# Teensylu-1_3.net
KiCad netlist of a schematic drawn in EAGLE
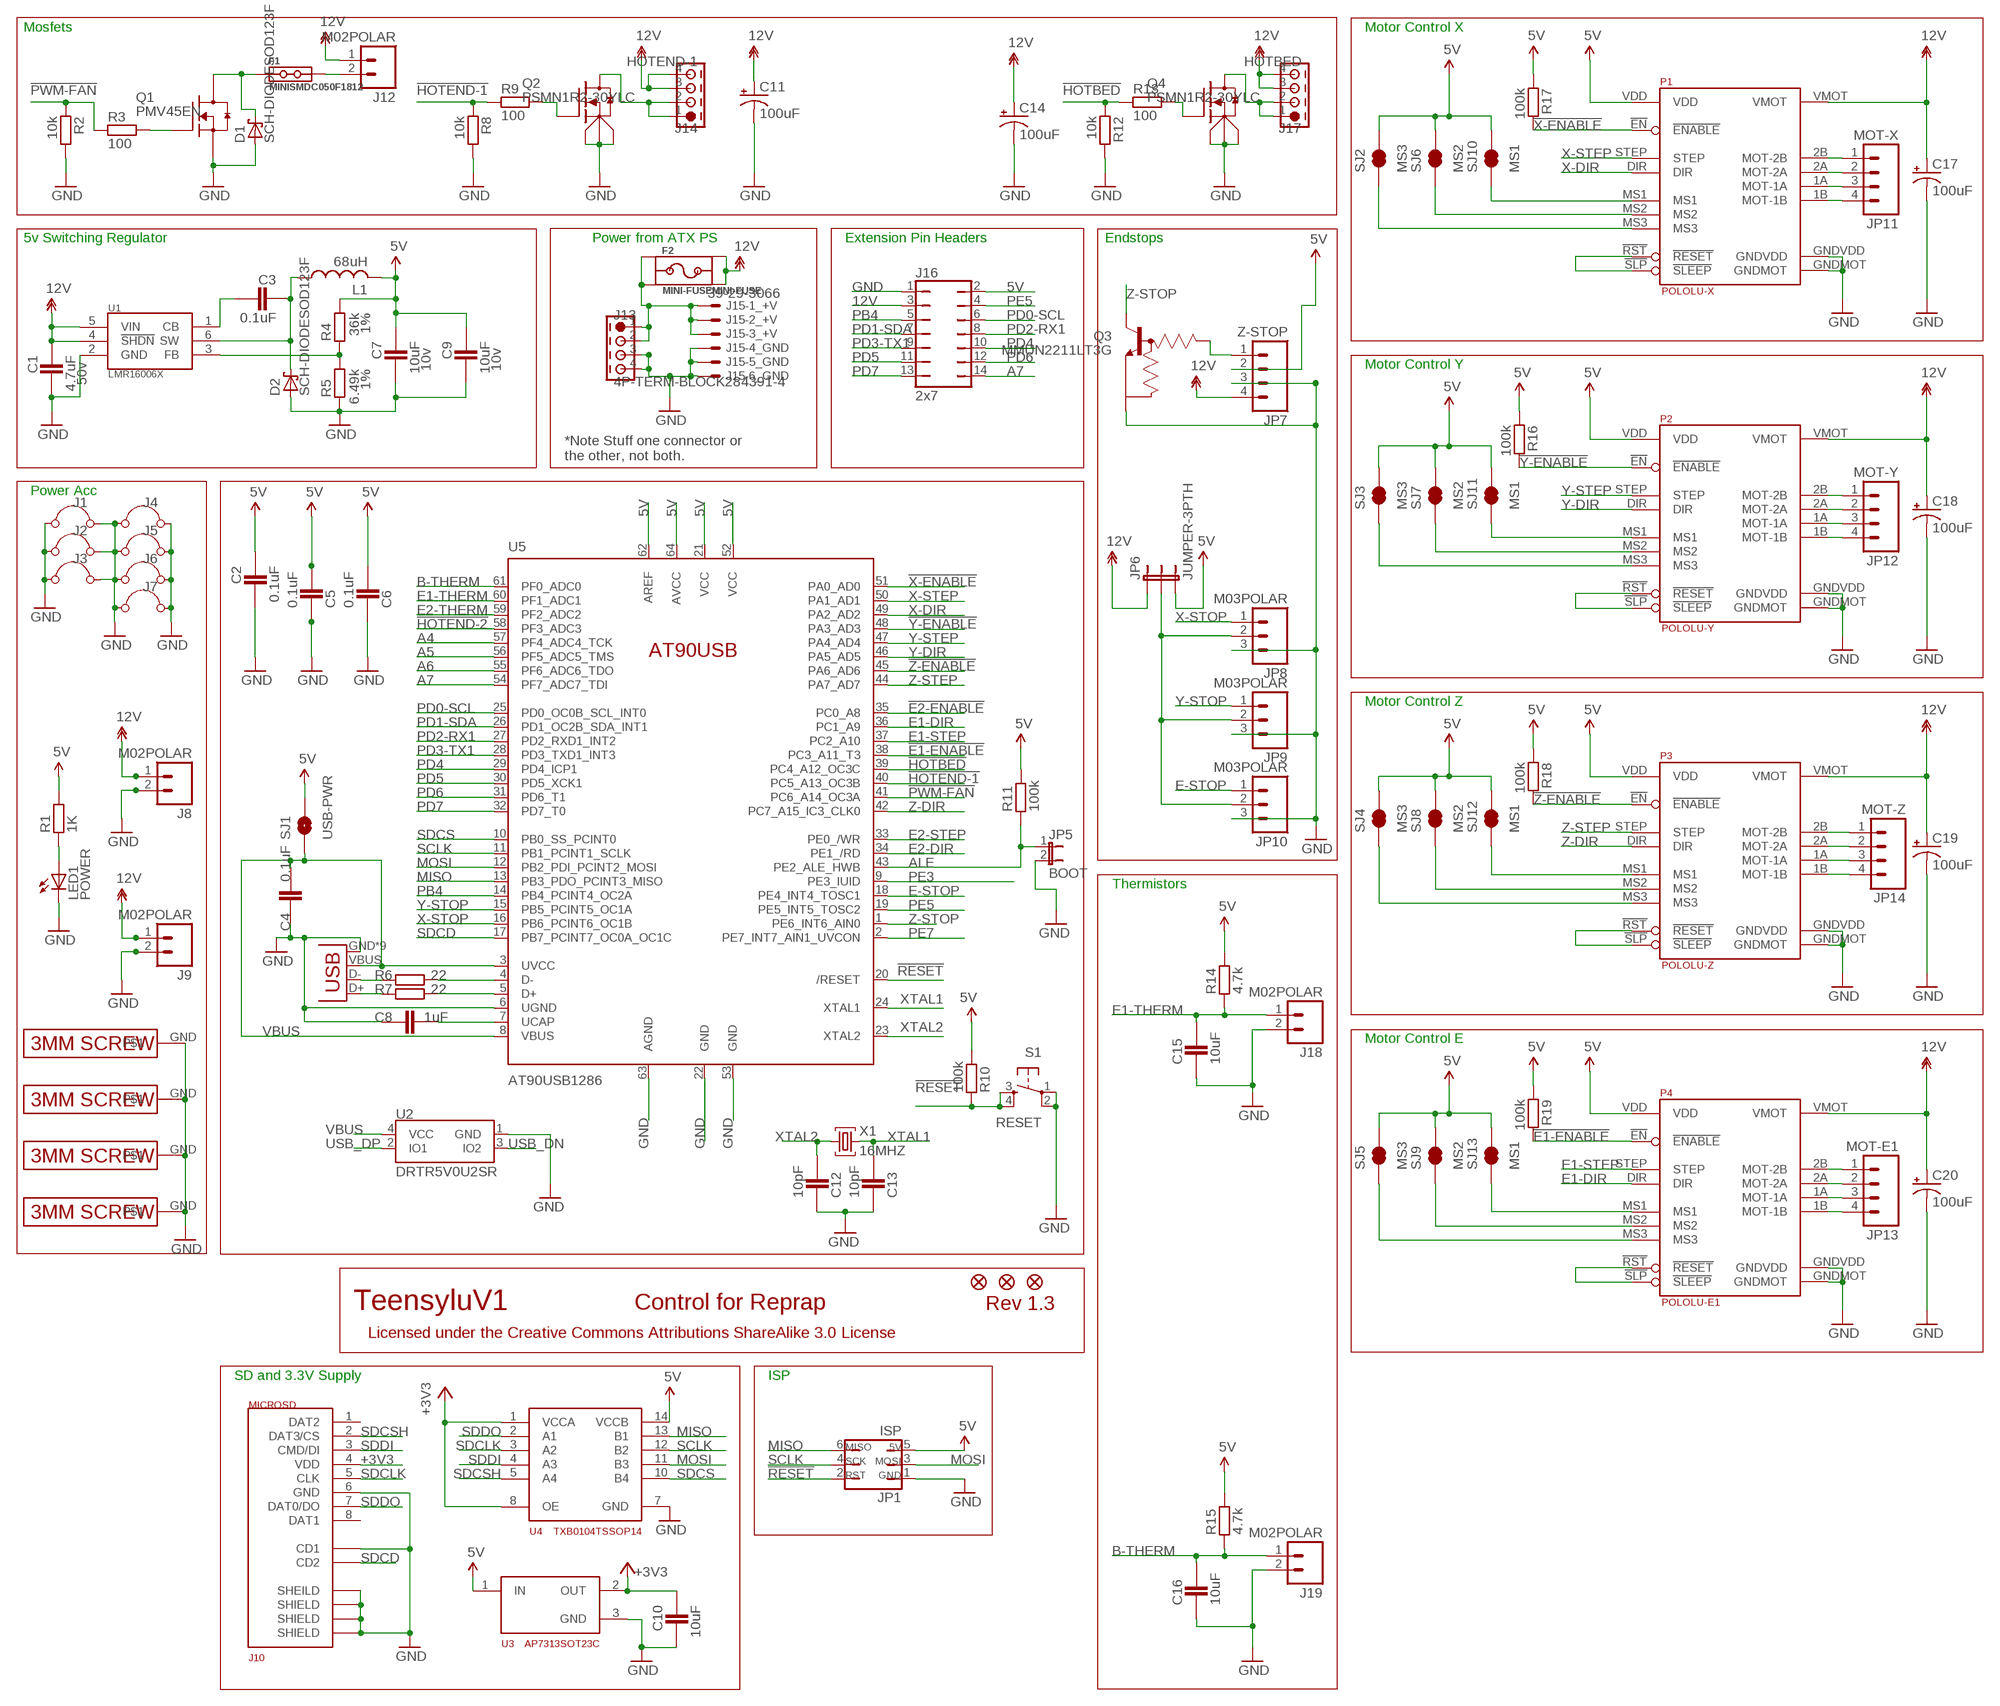
[diagram p0: schematic, sheet 1]

(export (version "E")
  (design (tool "Eeschema 10.0.6"))
  (components
    (comp (ref "C1")
      (value "4.7uF")
      (footprint "eagle-import:CAPC3215X168N")
      (fields
        (field (name "MANUFACTURER") "Yaiyo Yuden")
        (field (name "MANUFACTURER_PART_NUMBER") "UMK316AB7475KL-T")
        (field (name "TOLERANCE") "10%")
        (field (name "VDC") "50v")
      )
      (libsource (lib "eagle-import") (part "CAPACITOR_1206"))
    )
    (comp (ref "C2")
      (value "0.1uF")
      (footprint "eagle-import:CAPC1608X92N")
      (fields
        (field (name "MANUFACTURER") "Murata")
        (field (name "MANUFACTURER_PART_NUMBER") "GRM188R71C104KA01D")
        (field (name "TOLERANCE") "10%")
      )
      (libsource (lib "eagle-import") (part "CAPACITOR_0603"))
    )
    (comp (ref "C3")
      (value "0.1uF")
      (footprint "eagle-import:CAPC1608X92N")
      (fields
        (field (name "MANUFACTURER") "Samsung")
        (field (name "MANUFACTURER_PART_NUMBER") "CL10B104KB8NNNC")
        (field (name "TOLERANCE") "10%")
      )
      (libsource (lib "eagle-import") (part "CAPACITOR_0603"))
    )
    (comp (ref "C4")
      (value "0.1uF")
      (footprint "eagle-import:CAPC1608X92N")
      (fields
        (field (name "MANUFACTURER") "Murata")
        (field (name "MANUFACTURER_PART_NUMBER") "GRM188R71C104KA01D")
        (field (name "TOLERANCE") "10%")
      )
      (libsource (lib "eagle-import") (part "CAPACITOR_0603"))
    )
    (comp (ref "C5")
      (value "0.1uF")
      (footprint "eagle-import:CAPC1608X92N")
      (fields
        (field (name "MANUFACTURER") "Murata")
        (field (name "MANUFACTURER_PART_NUMBER") "GRM188R71C104KA01D")
        (field (name "TOLERANCE") "10%")
      )
      (libsource (lib "eagle-import") (part "CAPACITOR_0603"))
    )
    (comp (ref "C6")
      (value "0.1uF")
      (footprint "eagle-import:CAPC1608X92N")
      (fields
        (field (name "MANUFACTURER") "Murata")
        (field (name "MANUFACTURER_PART_NUMBER") "GRM188R71C104KA01D")
        (field (name "TOLERANCE") "10%")
      )
      (libsource (lib "eagle-import") (part "CAPACITOR_0603"))
    )
    (comp (ref "C7")
      (value "10uF")
      (footprint "eagle-import:CAPC2012X145AN")
      (fields
        (field (name "MANUFACTURER") "Murata")
        (field (name "MANUFACTURER_PART_NUMBER") "GRM21BR71A106KE51L")
        (field (name "TOLERANCE") "10%")
        (field (name "VDC") "10v")
      )
      (libsource (lib "eagle-import") (part "CAPACITOR_0805"))
    )
    (comp (ref "C8")
      (value "1uF")
      (footprint "eagle-import:CAPC1608X92N")
      (fields
        (field (name "MANUFACTURER") "Samsung")
        (field (name "MANUFACTURER_PART_NUMBER") "CL10A105MO8NNNC")
        (field (name "TOLERANCE") "20%")
      )
      (libsource (lib "eagle-import") (part "CAPACITOR_0603"))
    )
    (comp (ref "C9")
      (value "10uF")
      (footprint "eagle-import:CAPC2012X145AN")
      (fields
        (field (name "MANUFACTURER") "Murata")
        (field (name "MANUFACTURER_PART_NUMBER") "GRM21BR71A106KE51L")
        (field (name "TOLERANCE") "10%")
        (field (name "VDC") "10v")
      )
      (libsource (lib "eagle-import") (part "CAPACITOR_0805"))
    )
    (comp (ref "C10")
      (value "10uF")
      (footprint "eagle-import:CAPC1608X92N")
      (fields
        (field (name "MANUFACTURER") "Murata")
        (field (name "MANUFACTURER_PART_NUMBER") "GRM188R61C106MA73D")
        (field (name "TOLERANCE") "20%")
      )
      (libsource (lib "eagle-import") (part "CAPACITOR_0603"))
    )
    (comp (ref "C11")
      (value "100uF")
      (footprint "eagle-import:PANASONIC_D")
      (fields
        (field (name "MANUFACTURER") "Panasonic")
        (field (name "MANUFACTURER_PART_NUMBER") "EEE-FTH101XAP")
        (field (name "TOLERANCE") "20%")
      )
      (libsource (lib "eagle-import") (part "CPOL-USD"))
    )
    (comp (ref "C12")
      (value "10pF")
      (footprint "eagle-import:CAPC1608X92N")
      (fields
        (field (name "MANUFACTURER") "Samsung")
        (field (name "MANUFACTURER_PART_NUMBER") "CL10C100JB8NCNC")
        (field (name "TOLERANCE") "5%")
      )
      (libsource (lib "eagle-import") (part "CAPACITOR_0603"))
    )
    (comp (ref "C13")
      (value "10pF")
      (footprint "eagle-import:CAPC1608X92N")
      (fields
        (field (name "MANUFACTURER") "Samsung")
        (field (name "MANUFACTURER_PART_NUMBER") "CL10C100JB8NCNC")
        (field (name "TOLERANCE") "5%")
      )
      (libsource (lib "eagle-import") (part "CAPACITOR_0603"))
    )
    (comp (ref "C14")
      (value "100uF")
      (footprint "eagle-import:PANASONIC_D")
      (fields
        (field (name "MANUFACTURER") "Panasonic")
        (field (name "MANUFACTURER_PART_NUMBER") "EEE-FTH101XAP")
        (field (name "TOLERANCE") "20%")
      )
      (libsource (lib "eagle-import") (part "CPOL-USD"))
    )
    (comp (ref "C15")
      (value "10uF")
      (footprint "eagle-import:CAPC1608X92N")
      (fields
        (field (name "MANUFACTURER") "Murata")
        (field (name "MANUFACTURER_PART_NUMBER") "GRM188R61C106MA73D")
        (field (name "TOLERANCE") "20%")
      )
      (libsource (lib "eagle-import") (part "CAPACITOR_0603"))
    )
    (comp (ref "C16")
      (value "10uF")
      (footprint "eagle-import:CAPC1608X92N")
      (fields
        (field (name "MANUFACTURER") "Murata")
        (field (name "MANUFACTURER_PART_NUMBER") "GRM188R61C106MA73D")
        (field (name "TOLERANCE") "20%")
      )
      (libsource (lib "eagle-import") (part "CAPACITOR_0603"))
    )
    (comp (ref "C17")
      (value "100uF")
      (footprint "eagle-import:PANASONIC_D")
      (fields
        (field (name "MANUFACTURER") "Panasonic")
        (field (name "MANUFACTURER_PART_NUMBER") "EEE-FTH101XAP")
        (field (name "TOLERANCE") "20%")
      )
      (libsource (lib "eagle-import") (part "CPOL-USD"))
    )
    (comp (ref "C18")
      (value "100uF")
      (footprint "eagle-import:PANASONIC_D")
      (fields
        (field (name "MANUFACTURER") "Panasonic")
        (field (name "MANUFACTURER_PART_NUMBER") "EEE-FTH101XAP")
        (field (name "TOLERANCE") "20%")
      )
      (libsource (lib "eagle-import") (part "CPOL-USD"))
    )
    (comp (ref "C19")
      (value "100uF")
      (footprint "eagle-import:PANASONIC_D")
      (fields
        (field (name "MANUFACTURER") "Panasonic")
        (field (name "MANUFACTURER_PART_NUMBER") "EEE-FTH101XAP")
        (field (name "TOLERANCE") "20%")
      )
      (libsource (lib "eagle-import") (part "CPOL-USD"))
    )
    (comp (ref "C20")
      (value "100uF")
      (footprint "eagle-import:PANASONIC_D")
      (fields
        (field (name "MANUFACTURER") "Panasonic")
        (field (name "MANUFACTURER_PART_NUMBER") "EEE-FTH101XAP")
        (field (name "TOLERANCE") "20%")
      )
      (libsource (lib "eagle-import") (part "CPOL-USD"))
    )
    (comp (ref "D1")
      (value "SCH-DIODESOD123F")
      (footprint "eagle-import:SOD123F")
      (fields
        (field (name "MANUFACTURER") "NXP Semiconductors")
        (field (name "MANUFACTURER_PART_NUMBER") "PMEG4010CEH,115")
        (field (name "CURRENT") "1A")
        (field (name "MANUFACTURER_1") "NXP Semiconductors")
      )
      (libsource (lib "eagle-import") (part "SCH-DIODESOD123F"))
    )
    (comp (ref "D2")
      (value "SCH-DIODESOD123F")
      (footprint "eagle-import:SOD123F")
      (fields
        (field (name "MANUFACTURER") "NXP Semiconductors")
        (field (name "MANUFACTURER_PART_NUMBER") "PMEG4010CEH,115")
        (field (name "CURRENT") "1A")
        (field (name "MANUFACTURER_1") "NXP Semiconductors")
        (field (name "MANUFACTURER_PART_NUMBER_1") "PMEG4010CEH,115")
        (field (name "REVERSE_VOLTAGE") "40V")
      )
      (libsource (lib "eagle-import") (part "SCH-DIODESOD123F"))
    )
    (comp (ref "F1")
      (value "MINISMDC050F1812")
      (footprint "eagle-import:MINISMDC")
      (fields
        (field (name "MANUFACTURER") "TE Connectivity")
        (field (name "MANUFACTURER_PART_NUMBER") "MINISMDC050F-2")
      )
      (libsource (lib "eagle-import") (part "MINISMDC050F1812"))
    )
    (comp (ref "F2")
      (value "MINI-FUSEMINI-FUSE")
      (footprint "eagle-import:MINI_FUSE")
      (fields (field (name "MANUFACTURER") "Keystone") (field (name "MANUFACTURER_PART_NUMBER") "3568"))
      (libsource (lib "eagle-import") (part "MINI-FUSEMINI-FUSE"))
    )
    (comp (ref "J1")
      (value "22ga")
      (footprint "eagle-import:WJ_01_08")
      (description "22ga jumper wire")
      (libsource (lib "eagle-import") (part "WIRE_JUMPER-0.1"))
    )
    (comp (ref "J2")
      (value "22ga")
      (footprint "eagle-import:WJ_01_08")
      (description "22ga jumper wire")
      (libsource (lib "eagle-import") (part "WIRE_JUMPER-0.1"))
    )
    (comp (ref "J3")
      (value "22ga")
      (footprint "eagle-import:WJ_01_08")
      (description "22ga jumper wire")
      (libsource (lib "eagle-import") (part "WIRE_JUMPER-0.1"))
    )
    (comp (ref "J4")
      (value "22ga")
      (footprint "eagle-import:WJ_01_08")
      (description "22ga jumper wire")
      (libsource (lib "eagle-import") (part "WIRE_JUMPER-0.1"))
    )
    (comp (ref "J5")
      (value "22ga")
      (footprint "eagle-import:WJ_01_08")
      (description "22ga jumper wire")
      (libsource (lib "eagle-import") (part "WIRE_JUMPER-0.1"))
    )
    (comp (ref "J6")
      (value "22ga")
      (footprint "eagle-import:WJ_01_08")
      (description "22ga jumper wire")
      (libsource (lib "eagle-import") (part "WIRE_JUMPER-0.1"))
    )
    (comp (ref "J7")
      (value "22ga")
      (footprint "eagle-import:WJ_01_08")
      (description "22ga jumper wire")
      (libsource (lib "eagle-import") (part "WIRE_JUMPER-0.1"))
    )
    (comp (ref "J8")
      (value "M02POLAR")
      (footprint "eagle-import:MOLEX-1X2")
      (description "CONN HEADER 2POS .100 VERT TIN")
      (fields (field (name "MANUFACTURER") "Molex") (field (name "MANUFACTURER_PART_NUMBER") "0022272021"))
      (libsource (lib "eagle-import") (part "M02POLAR"))
    )
    (comp (ref "J9")
      (value "M02POLAR")
      (footprint "eagle-import:MOLEX-1X2")
      (description "CONN HEADER 2POS .100 VERT TIN")
      (fields (field (name "MANUFACTURER") "Molex") (field (name "MANUFACTURER_PART_NUMBER") "0022272021"))
      (libsource (lib "eagle-import") (part "M02POLAR"))
    )
    (comp (ref "J10")
      (value "MICROSD")
      (footprint "eagle-import:AMPHENOL-MICROSD")
      (description "CONN MICRO SD CARD PUSH-PULL R/A")
      (fields
        (field (name "MANUFACTURER") "Amphenol")
        (field (name "MANUFACTURER_PART_NUMBER") "114-00841-68")
      )
      (libsource (lib "eagle-import") (part "MICROSD"))
    )
    (comp (ref "J11")
      (value "USB-MICRO-PTH")
      (footprint "eagle-import:USB-MICROB-PTH")
      (fields (field (name "MANUFACTURER") "FCI") (field (name "MANUFACTURER_PART_NUMBER") "10118194-0001LF"))
      (libsource (lib "eagle-import") (part "USB-MICRO-PTH"))
    )
    (comp (ref "J12")
      (value "M02POLAR")
      (footprint "eagle-import:MOLEX-1X2")
      (description "CONN HEADER 2POS .100 VERT TIN")
      (fields (field (name "MANUFACTURER") "Molex") (field (name "MANUFACTURER_PART_NUMBER") "0022272021"))
      (libsource (lib "eagle-import") (part "M02POLAR"))
    )
    (comp (ref "J13")
      (value "4P-TERM-BLOCK284391-4")
      (footprint "eagle-import:284391-4")
      (fields
        (field (name "MANUFACTURER") "TE Connectivity")
        (field (name "MANUFACTURER_PART_NUMBER") "284391-4")
      )
      (libsource (lib "eagle-import") (part "4P-TERM-BLOCK284391-4"))
    )
    (comp (ref "J14")
      (value "HOTEND-1")
      (footprint "eagle-import:284391-4")
      (fields
        (field (name "MANUFACTURER") "TE Connectivity")
        (field (name "MANUFACTURER_PART_NUMBER") "284391-4")
      )
      (libsource (lib "eagle-import") (part "4P-TERM-BLOCK284391-4"))
    )
    (comp (ref "J15")
      (value "39-29-3066")
      (footprint "eagle-import:39-29-3066")
      (fields (field (name "MANUFACTURER") "Molex") (field (name "MANUFACTURER_PART_NUMBER") "0039293066"))
      (libsource (lib "eagle-import") (part "39-29-3066"))
    )
    (comp (ref "J16")
      (value "2x7")
      (footprint "eagle-import:JP7Q")
      (description "DIL VERTICAL PC TAIL PIN HEADER")
      (fields (field (name "MANUFACTURER") "Harwin") (field (name "MANUFACTURER_PART_NUMBER") "M20-9980746"))
      (libsource (lib "eagle-import") (part "JP7Q"))
    )
    (comp (ref "J17")
      (value "HOTBED")
      (footprint "eagle-import:284391-4")
      (fields
        (field (name "MANUFACTURER") "TE Connectivity")
        (field (name "MANUFACTURER_PART_NUMBER") "284391-4")
      )
      (libsource (lib "eagle-import") (part "4P-TERM-BLOCK284391-4"))
    )
    (comp (ref "J18")
      (value "M02POLAR")
      (footprint "eagle-import:MOLEX-1X2")
      (description "CONN HEADER 2POS .100 VERT TIN")
      (fields (field (name "MANUFACTURER") "Molex") (field (name "MANUFACTURER_PART_NUMBER") "0022272021"))
      (libsource (lib "eagle-import") (part "M02POLAR"))
    )
    (comp (ref "J19")
      (value "M02POLAR")
      (footprint "eagle-import:MOLEX-1X2")
      (description "CONN HEADER 2POS .100 VERT TIN")
      (fields (field (name "MANUFACTURER") "Molex") (field (name "MANUFACTURER_PART_NUMBER") "0022272021"))
      (libsource (lib "eagle-import") (part "M02POLAR"))
    )
    (comp (ref "JP1")
      (value "ISP")
      (footprint "eagle-import:ISP")
      (libsource (lib "eagle-import") (part "PROGHEADER"))
    )
    (comp (ref "JP2")
      (value "FIDUCIAL1X2.5")
      (footprint "eagle-import:FIDUCIAL-1X2.5")
      (libsource (lib "eagle-import") (part "FIDUCIAL1X2.5"))
    )
    (comp (ref "JP3")
      (value "FIDUCIAL1X2.5")
      (footprint "eagle-import:FIDUCIAL-1X2.5")
      (libsource (lib "eagle-import") (part "FIDUCIAL1X2.5"))
    )
    (comp (ref "JP4")
      (value "FIDUCIAL1X2.5")
      (footprint "eagle-import:FIDUCIAL-1X2.5")
      (libsource (lib "eagle-import") (part "FIDUCIAL1X2.5"))
    )
    (comp (ref "JP5")
      (value "BOOT")
      (footprint "eagle-import:1X02")
      (description "SIL VERTICAL PC TAIL PIN HEADER")
      (fields (field (name "MANUFACTURER") "Harwin") (field (name "MANUFACTURER_PART_NUMBER") "M20-9990246"))
      (libsource (lib "eagle-import") (part "JUMPER-2PTH"))
    )
    (comp (ref "JP6")
      (value "JUMPER-3PTH")
      (footprint "eagle-import:1X03")
      (libsource (lib "eagle-import") (part "JUMPER-3PTH"))
    )
    (comp (ref "JP7")
      (value "Z-STOP")
      (footprint "eagle-import:MOLEX-1X4")
      (fields (field (name "MANUFACTURER") "Molex") (field (name "MANUFACTURER_PART_NUMBER") "0022272041"))
      (libsource (lib "eagle-import") (part "M04POLAR"))
    )
    (comp (ref "JP8")
      (value "M03POLAR")
      (footprint "eagle-import:MOLEX-1X3")
      (description "CONN HEADER 3POS .100 VERT TIN")
      (fields (field (name "MANUFACTURER") "Molex") (field (name "MANUFACTURER_PART_NUMBER") "0022272031"))
      (libsource (lib "eagle-import") (part "M03POLAR"))
    )
    (comp (ref "JP9")
      (value "M03POLAR")
      (footprint "eagle-import:MOLEX-1X3")
      (description "CONN HEADER 3POS .100 VERT TIN")
      (fields (field (name "MANUFACTURER") "Molex") (field (name "MANUFACTURER_PART_NUMBER") "0022272031"))
      (libsource (lib "eagle-import") (part "M03POLAR"))
    )
    (comp (ref "JP10")
      (value "M03POLAR")
      (footprint "eagle-import:MOLEX-1X3")
      (description "CONN HEADER 3POS .100 VERT TIN")
      (fields (field (name "MANUFACTURER") "Molex") (field (name "MANUFACTURER_PART_NUMBER") "0022272031"))
      (libsource (lib "eagle-import") (part "M03POLAR"))
    )
    (comp (ref "JP11")
      (value "MOT-X")
      (footprint "eagle-import:MOLEX-1X4")
      (fields (field (name "MANUFACTURER") "Molex") (field (name "MANUFACTURER_PART_NUMBER") "0022272041"))
      (libsource (lib "eagle-import") (part "M04POLAR"))
    )
    (comp (ref "JP12")
      (value "MOT-Y")
      (footprint "eagle-import:MOLEX-1X4")
      (fields (field (name "MANUFACTURER") "Molex") (field (name "MANUFACTURER_PART_NUMBER") "0022272041"))
      (libsource (lib "eagle-import") (part "M04POLAR"))
    )
    (comp (ref "JP13")
      (value "MOT-E1")
      (footprint "eagle-import:MOLEX-1X4")
      (fields (field (name "MANUFACTURER") "Molex") (field (name "MANUFACTURER_PART_NUMBER") "0022272041"))
      (libsource (lib "eagle-import") (part "M04POLAR"))
    )
    (comp (ref "JP14")
      (value "MOT-Z")
      (footprint "eagle-import:MOLEX-1X4")
      (fields (field (name "MANUFACTURER") "Molex") (field (name "MANUFACTURER_PART_NUMBER") "0022272041"))
      (libsource (lib "eagle-import") (part "M04POLAR"))
    )
    (comp (ref "L1")
      (value "68uH")
      (footprint "eagle-import:SRN6045")
      (fields
        (field (name "MANUFACTURER") "Bourns")
        (field (name "MANUFACTURER_PART_NUMBER") "SRN6045-680M")
        (field (name "MANUFACTURER_1") "Bourns")
        (field (name "MANUFACTURER_PART_NUMBER_1") "SRN6045-680M")
      )
      (libsource (lib "eagle-import") (part "INDUCTORSRN6045"))
    )
    (comp (ref "LED1")
      (value "POWER")
      (footprint "eagle-import:CHIPLED_0805")
      (fields
        (field (name "MANUFACTURER") "Kingbright")
        (field (name "MANUFACTURER_PART_NUMBER") "APT2012SGC")
      )
      (libsource (lib "eagle-import") (part "LEDCHIPLED_0805"))
    )
    (comp (ref "P1")
      (value "POLOLU-X")
      (footprint "eagle-import:POLOLU-STEPPER-PTH")
      (libsource (lib "eagle-import") (part "POLOLU-ALLEGRO"))
    )
    (comp (ref "P2")
      (value "POLOLU-Y")
      (footprint "eagle-import:POLOLU-STEPPER-PTH")
      (libsource (lib "eagle-import") (part "POLOLU-ALLEGRO"))
    )
    (comp (ref "P3")
      (value "POLOLU-Z")
      (footprint "eagle-import:POLOLU-STEPPER-PTH")
      (libsource (lib "eagle-import") (part "POLOLU-ALLEGRO"))
    )
    (comp (ref "P4")
      (value "POLOLU-E1")
      (footprint "eagle-import:POLOLU-STEPPER-PTH")
      (libsource (lib "eagle-import") (part "POLOLU-ALLEGRO"))
    )
    (comp (ref "Q1")
      (value "PMV45EN")
      (footprint "eagle-import:SOT23C")
      (fields
        (field (name "MANUFACTURER") "International Rectifier")
        (field (name "MANUFACTURER_PART_NUMBER") "IRLML2060TRPBF")
        (field (name "VOLTAGE") "60V")
      )
      (libsource (lib "eagle-import") (part "MOSFET-NCH_SOT-23"))
    )
    (comp (ref "Q2")
      (value "PSMN1R2-30YLC")
      (footprint "eagle-import:LFPACK-POWERPAK-SO8")
      (fields
        (field (name "MANUFACTURER") "NXP Semiconductors")
        (field (name "MANUFACTURER_PART_NUMBER") "PSMN1R2-30YLC,115")
        (field (name "VOLTAGE") "30V")
      )
      (libsource (lib "eagle-import") (part "PSMN1R2-30YLCPOWERPACK-S08"))
    )
    (comp (ref "Q3")
      (value "MMUN2211LT3G")
      (footprint "eagle-import:SOT23C")
      (description "TRANS PREBIAS NPN 246MW SOT23-3")
      (fields (field (name "MANUFACTURER") "ON Semiconductor"))
      (libsource (lib "eagle-import") (part "TRANSISTOR_NPN_BIASSOT23C"))
    )
    (comp (ref "Q4")
      (value "PSMN1R2-30YLC")
      (footprint "eagle-import:LFPACK-POWERPAK-SO8")
      (fields
        (field (name "MANUFACTURER") "NXP Semiconductors")
        (field (name "MANUFACTURER_PART_NUMBER") "PSMN1R2-30YLC,115")
        (field (name "VOLTAGE") "30V")
      )
      (libsource (lib "eagle-import") (part "PSMN1R2-30YLCPOWERPACK-S08"))
    )
    (comp (ref "R1")
      (value "1K")
      (footprint "eagle-import:RESC1608X55N")
      (libsource (lib "eagle-import") (part "RESISTOR_0603"))
    )
    (comp (ref "R2")
      (value "10k")
      (footprint "eagle-import:RESC1608X55N")
      (libsource (lib "eagle-import") (part "RESISTOR_0603"))
    )
    (comp (ref "R3")
      (value "100")
      (footprint "eagle-import:RESC1608X55N")
      (libsource (lib "eagle-import") (part "RESISTOR_0603"))
    )
    (comp (ref "R4")
      (value "36k")
      (footprint "eagle-import:RESC1608X55N")
      (fields (field (name "TOLERANCE") "1%"))
      (libsource (lib "eagle-import") (part "RESISTOR_0603"))
    )
    (comp (ref "R5")
      (value "6.49k")
      (footprint "eagle-import:RESC1608X55N")
      (fields (field (name "TOLERANCE") "1%"))
      (libsource (lib "eagle-import") (part "RESISTOR_0603"))
    )
    (comp (ref "R6")
      (value "22")
      (footprint "eagle-import:RESC1608X55N")
      (libsource (lib "eagle-import") (part "RESISTOR_0603"))
    )
    (comp (ref "R7")
      (value "22")
      (footprint "eagle-import:RESC1608X55N")
      (libsource (lib "eagle-import") (part "RESISTOR_0603"))
    )
    (comp (ref "R8")
      (value "10k")
      (footprint "eagle-import:RESC1608X55N")
      (libsource (lib "eagle-import") (part "RESISTOR_0603"))
    )
    (comp (ref "R9")
      (value "100")
      (footprint "eagle-import:RESC1608X55N")
      (libsource (lib "eagle-import") (part "RESISTOR_0603"))
    )
    (comp (ref "R10")
      (value "100k")
      (footprint "eagle-import:RESC1608X55N")
      (libsource (lib "eagle-import") (part "RESISTOR_0603"))
    )
    (comp (ref "R11")
      (value "100k")
      (footprint "eagle-import:RESC1608X55N")
      (libsource (lib "eagle-import") (part "RESISTOR_0603"))
    )
    (comp (ref "R12")
      (value "10k")
      (footprint "eagle-import:RESC1608X55N")
      (libsource (lib "eagle-import") (part "RESISTOR_0603"))
    )
    (comp (ref "R13")
      (value "100")
      (footprint "eagle-import:RESC1608X55N")
      (libsource (lib "eagle-import") (part "RESISTOR_0603"))
    )
    (comp (ref "R14")
      (value "4.7k")
      (footprint "eagle-import:RESC1608X55N")
      (libsource (lib "eagle-import") (part "RESISTOR_0603"))
    )
    (comp (ref "R15")
      (value "4.7k")
      (footprint "eagle-import:RESC1608X55N")
      (libsource (lib "eagle-import") (part "RESISTOR_0603"))
    )
    (comp (ref "R16")
      (value "100k")
      (footprint "eagle-import:RESC1608X55N")
      (libsource (lib "eagle-import") (part "RESISTOR_0603"))
    )
    (comp (ref "R17")
      (value "100k")
      (footprint "eagle-import:RESC1608X55N")
      (libsource (lib "eagle-import") (part "RESISTOR_0603"))
    )
    (comp (ref "R18")
      (value "100k")
      (footprint "eagle-import:RESC1608X55N")
      (libsource (lib "eagle-import") (part "RESISTOR_0603"))
    )
    (comp (ref "R19")
      (value "100k")
      (footprint "eagle-import:RESC1608X55N")
      (libsource (lib "eagle-import") (part "RESISTOR_0603"))
    )
    (comp (ref "S1")
      (value "RESET")
      (footprint "eagle-import:TACTILE_SWITCH_SMD")
      (fields (field (name "MANUFACTURER") "Bourns") (field (name "MANUFACTURER_PART_NUMBER") "7914J-1-000E"))
      (libsource (lib "eagle-import") (part "TAC_SWITCHSMD"))
    )
    (comp (ref "SCREW1")
      (value "3MM-SCREW")
      (footprint "eagle-import:PLATEDSCREW")
      (libsource (lib "eagle-import") (part "3MM-SCREW"))
    )
    (comp (ref "SCREW2")
      (value "3MM-SCREW")
      (footprint "eagle-import:PLATEDSCREW")
      (libsource (lib "eagle-import") (part "3MM-SCREW"))
    )
    (comp (ref "SCREW3")
      (value "3MM-SCREW")
      (footprint "eagle-import:PLATEDSCREW")
      (libsource (lib "eagle-import") (part "3MM-SCREW"))
    )
    (comp (ref "SCREW4")
      (value "3MM-SCREW")
      (footprint "eagle-import:PLATEDSCREW")
      (libsource (lib "eagle-import") (part "3MM-SCREW"))
    )
    (comp (ref "SJ1")
      (value "USB-PWR")
      (footprint "eagle-import:SJ_2S-NO")
      (libsource (lib "eagle-import") (part "SOLDERJUMPERNO"))
    )
    (comp (ref "SJ2")
      (value "MS3")
      (footprint "eagle-import:SJ_2S-TRACE")
      (libsource (lib "eagle-import") (part "SOLDERJUMPER-NCSJ-TRACE"))
    )
    (comp (ref "SJ3")
      (value "MS3")
      (footprint "eagle-import:SJ_2S-TRACE")
      (libsource (lib "eagle-import") (part "SOLDERJUMPER-NCSJ-TRACE"))
    )
    (comp (ref "SJ4")
      (value "MS3")
      (footprint "eagle-import:SJ_2S-TRACE")
      (libsource (lib "eagle-import") (part "SOLDERJUMPER-NCSJ-TRACE"))
    )
    (comp (ref "SJ5")
      (value "MS3")
      (footprint "eagle-import:SJ_2S-TRACE")
      (libsource (lib "eagle-import") (part "SOLDERJUMPER-NCSJ-TRACE"))
    )
    (comp (ref "SJ6")
      (value "MS2")
      (footprint "eagle-import:SJ_2S-TRACE")
      (libsource (lib "eagle-import") (part "SOLDERJUMPER-NCSJ-TRACE"))
    )
    (comp (ref "SJ7")
      (value "MS2")
      (footprint "eagle-import:SJ_2S-TRACE")
      (libsource (lib "eagle-import") (part "SOLDERJUMPER-NCSJ-TRACE"))
    )
    (comp (ref "SJ8")
      (value "MS2")
      (footprint "eagle-import:SJ_2S-TRACE")
      (libsource (lib "eagle-import") (part "SOLDERJUMPER-NCSJ-TRACE"))
    )
    (comp (ref "SJ9")
      (value "MS2")
      (footprint "eagle-import:SJ_2S-TRACE")
      (libsource (lib "eagle-import") (part "SOLDERJUMPER-NCSJ-TRACE"))
    )
    (comp (ref "SJ10")
      (value "MS1")
      (footprint "eagle-import:SJ_2S-TRACE")
      (libsource (lib "eagle-import") (part "SOLDERJUMPER-NCSJ-TRACE"))
    )
    (comp (ref "SJ11")
      (value "MS1")
      (footprint "eagle-import:SJ_2S-TRACE")
      (libsource (lib "eagle-import") (part "SOLDERJUMPER-NCSJ-TRACE"))
    )
    (comp (ref "SJ12")
      (value "MS1")
      (footprint "eagle-import:SJ_2S-TRACE")
      (libsource (lib "eagle-import") (part "SOLDERJUMPER-NCSJ-TRACE"))
    )
    (comp (ref "SJ13")
      (value "MS1")
      (footprint "eagle-import:SJ_2S-TRACE")
      (libsource (lib "eagle-import") (part "SOLDERJUMPER-NCSJ-TRACE"))
    )
    (comp (ref "U1")
      (value "LMR16006X")
      (footprint "eagle-import:TSOT6")
      (fields
        (field (name "MANUFACTURER") "Texas Instruments")
        (field (name "MANUFACTURER_PART_NUMBER") "LMR16006XDDCT")
      )
      (libsource (lib "eagle-import") (part "LMR16006X"))
    )
    (comp (ref "U2")
      (value "DRTR5V0U2SR")
      (footprint "eagle-import:SOT143-R")
      (fields
        (field (name "MANUFACTURER") "Diodes Incorporated")
        (field (name "MANUFACTURER_PART_NUMBER") "DTR5V0U2SR")
      )
      (libsource (lib "eagle-import") (part "DRTR5V0U2SR"))
    )
    (comp (ref "U3")
      (value "AP7313SOT23C")
      (footprint "eagle-import:SOT23C")
      (description "IC REG LDO 3.3V 0.15A SOT23-3")
      (fields
        (field (name "MANUFACTURER") "Diodes Incorporated")
        (field (name "MANUFACTURER_PART_NUMBER") "AP7313-33SAG-7")
      )
      (libsource (lib "eagle-import") (part "AP7313SOT23C"))
    )
    (comp (ref "U4")
      (value "TXB0104TSSOP14")
      (footprint "eagle-import:TSSOP14")
      (description "IC VOLT-LEVEL TRANSLATOR 14TSSOP")
      (fields
        (field (name "MANUFACTURER") "Texas Instruments")
        (field (name "MANUFACTURER_PART_NUMBER") "TXB0104PWR")
      )
      (libsource (lib "eagle-import") (part "TXB0104TSSOP14"))
    )
    (comp (ref "U5")
      (value "AT90USB1286")
      (footprint "eagle-import:TQFP64-2")
      (fields (field (name "MANUFACTURER") "Atmel"))
      (libsource (lib "eagle-import") (part "AT90USB"))
    )
    (comp (ref "X1")
      (value "16MHZ")
      (footprint "eagle-import:NDK-XTAL")
      (fields
        (field (name "MANUFACTURER") "NDK")
        (field (name "MANUFACTURER_PART_NUMBER") "NX5032GA-16.000000MHZ-LN-CD-1")
      )
      (libsource (lib "eagle-import") (part "XTAL"))
    )
  )
  (nets
    (net (code "1") (name "+3V3") (class "Default")
      (node (ref "C10") (pin "1") (pinfunction "1_1") (pintype "passive"))
      (node (ref "J10") (pin "4") (pinfunction "VDD_4") (pintype "power_in"))
      (node (ref "U3") (pin "2") (pinfunction "OUT_2") (pintype "power_in"))
      (node (ref "U4") (pin "1") (pinfunction "VCCA_1") (pintype "power_in"))
      (node (ref "U4") (pin "8") (pinfunction "OE_8") (pintype "input"))
    )
    (net (code "2") (name "/A4") (class "Default")
      (node (ref "U5") (pin "57") (pinfunction "PF4_ADC4_TCK_57") (pintype "bidirectional"))
    )
    (net (code "3") (name "/A5") (class "Default")
      (node (ref "U5") (pin "56") (pinfunction "PF5_ADC5_TMS_56") (pintype "bidirectional"))
    )
    (net (code "4") (name "/A6") (class "Default")
      (node (ref "U5") (pin "55") (pinfunction "PF6_ADC6_TDO_55") (pintype "bidirectional"))
    )
    (net (code "5") (name "/A7") (class "Default")
      (node (ref "J16") (pin "14") (pinfunction "14_14") (pintype "passive"))
      (node (ref "U5") (pin "54") (pinfunction "PF7_ADC7_TDI_54") (pintype "bidirectional"))
    )
    (net (code "6") (name "/ALE") (class "Default")
      (node (ref "JP5") (pin "1") (pinfunction "1_1") (pintype "passive"))
      (node (ref "R11") (pin "1") (pinfunction "1_1") (pintype "passive"))
      (node (ref "U5") (pin "43") (pinfunction "PE2_ALE_HWB_43") (pintype "bidirectional"))
    )
    (net (code "7") (name "/B-THERM") (class "Default")
      (node (ref "C16") (pin "2") (pinfunction "2_2") (pintype "passive"))
      (node (ref "J19") (pin "1") (pinfunction "1_1") (pintype "passive"))
      (node (ref "R15") (pin "1") (pinfunction "1_1") (pintype "passive"))
      (node (ref "U5") (pin "61") (pinfunction "PF0_ADC0_61") (pintype "bidirectional"))
    )
    (net (code "8") (name "/E-STOP") (class "Default")
      (node (ref "JP10") (pin "1") (pinfunction "1_1") (pintype "passive"))
      (node (ref "U5") (pin "18") (pinfunction "PE4_INT4_TOSC1_18") (pintype "bidirectional"))
    )
    (net (code "9") (name "/E1-DIR") (class "Default")
      (node (ref "P4") (pin "DIR") (pinfunction "DIR_DIR") (pintype "bidirectional"))
      (node (ref "U5") (pin "36") (pinfunction "PC1_A9_36") (pintype "bidirectional"))
    )
    (net (code "10") (name "/E1-STEP") (class "Default")
      (node (ref "P4") (pin "STEP") (pinfunction "STEP_STEP") (pintype "bidirectional"))
      (node (ref "U5") (pin "37") (pinfunction "PC2_A10_37") (pintype "bidirectional"))
    )
    (net (code "11") (name "/E1-THERM") (class "Default")
      (node (ref "C15") (pin "2") (pinfunction "2_2") (pintype "passive"))
      (node (ref "J18") (pin "1") (pinfunction "1_1") (pintype "passive"))
      (node (ref "R14") (pin "1") (pinfunction "1_1") (pintype "passive"))
      (node (ref "U5") (pin "60") (pinfunction "PF1_ADC1_60") (pintype "bidirectional"))
    )
    (net (code "12") (name "/E2-DIR") (class "Default")
      (node (ref "U5") (pin "34") (pinfunction "PE1_/RD_34") (pintype "bidirectional"))
    )
    (net (code "13") (name "/E2-STEP") (class "Default")
      (node (ref "U5") (pin "33") (pinfunction "PE0_/WR_33") (pintype "bidirectional"))
    )
    (net (code "14") (name "/E2-THERM") (class "Default")
      (node (ref "U5") (pin "59") (pinfunction "PF2_ADC2_59") (pintype "bidirectional"))
    )
    (net (code "15") (name "/MISO") (class "Default")
      (node (ref "JP1") (pin "6") (pinfunction "6_6") (pintype "passive"))
      (node (ref "U4") (pin "13") (pinfunction "B1_13") (pintype "bidirectional"))
      (node (ref "U5") (pin "13") (pinfunction "PB3_PDO_PCINT3_MISO_13") (pintype "bidirectional"))
    )
    (net (code "16") (name "/MOSI") (class "Default")
      (node (ref "JP1") (pin "3") (pinfunction "3_3") (pintype "passive"))
      (node (ref "U4") (pin "11") (pinfunction "B3_11") (pintype "bidirectional"))
      (node (ref "U5") (pin "12") (pinfunction "PB2_PDI_PCINT2_MOSI_12") (pintype "bidirectional"))
    )
    (net (code "17") (name "/PB4") (class "Default")
      (node (ref "J16") (pin "5") (pinfunction "5_5") (pintype "passive"))
      (node (ref "U5") (pin "14") (pinfunction "PB4_PCINT4_OC2A_14") (pintype "bidirectional"))
    )
    (net (code "18") (name "/PD0-SCL") (class "Default")
      (node (ref "J16") (pin "6") (pinfunction "6_6") (pintype "passive"))
      (node (ref "U5") (pin "25") (pinfunction "PD0_OC0B_SCL_INT0_25") (pintype "bidirectional"))
    )
    (net (code "19") (name "/PD1-SDA") (class "Default")
      (node (ref "J16") (pin "7") (pinfunction "7_7") (pintype "passive"))
      (node (ref "U5") (pin "26") (pinfunction "PD1_OC2B_SDA_INT1_26") (pintype "bidirectional"))
    )
    (net (code "20") (name "/PD2-RX1") (class "Default")
      (node (ref "J16") (pin "8") (pinfunction "8_8") (pintype "passive"))
      (node (ref "U5") (pin "27") (pinfunction "PD2_RXD1_INT2_27") (pintype "bidirectional"))
    )
    (net (code "21") (name "/PD3-TX1") (class "Default")
      (node (ref "J16") (pin "9") (pinfunction "9_9") (pintype "passive"))
      (node (ref "U5") (pin "28") (pinfunction "PD3_TXD1_INT3_28") (pintype "bidirectional"))
    )
    (net (code "22") (name "/PD4") (class "Default")
      (node (ref "J16") (pin "10") (pinfunction "10_10") (pintype "passive"))
      (node (ref "U5") (pin "29") (pinfunction "PD4_ICP1_29") (pintype "bidirectional"))
    )
    (net (code "23") (name "/PD5") (class "Default")
      (node (ref "J16") (pin "11") (pinfunction "11_11") (pintype "passive"))
      (node (ref "U5") (pin "30") (pinfunction "PD5_XCK1_30") (pintype "bidirectional"))
    )
    (net (code "24") (name "/PD6") (class "Default")
      (node (ref "J16") (pin "12") (pinfunction "12_12") (pintype "passive"))
      (node (ref "U5") (pin "31") (pinfunction "PD6_T1_31") (pintype "bidirectional"))
    )
    (net (code "25") (name "/PD7") (class "Default")
      (node (ref "J16") (pin "13") (pinfunction "13_13") (pintype "passive"))
      (node (ref "U5") (pin "32") (pinfunction "PD7_T0_32") (pintype "bidirectional"))
    )
    (net (code "26") (name "/PE3") (class "Default")
      (node (ref "U5") (pin "9") (pinfunction "PE3_IUID_9") (pintype "bidirectional"))
    )
    (net (code "27") (name "/PE5") (class "Default")
      (node (ref "J16") (pin "4") (pinfunction "4_4") (pintype "passive"))
      (node (ref "U5") (pin "19") (pinfunction "PE5_INT5_TOSC2_19") (pintype "bidirectional"))
    )
    (net (code "28") (name "/PE7") (class "Default")
      (node (ref "U5") (pin "2") (pinfunction "PE7_INT7_AIN1_UVCON_2") (pintype "bidirectional"))
    )
    (net (code "29") (name "/SCLK") (class "Default")
      (node (ref "JP1") (pin "4") (pinfunction "4_4") (pintype "passive"))
      (node (ref "U4") (pin "12") (pinfunction "B2_12") (pintype "bidirectional"))
      (node (ref "U5") (pin "11") (pinfunction "PB1_PCINT1_SCLK_11") (pintype "bidirectional"))
    )
    (net (code "30") (name "/SDCD") (class "Default")
      (node (ref "J10") (pin "CD2") (pinfunction "CD2_CD2") (pintype "bidirectional"))
      (node (ref "U5") (pin "17") (pinfunction "PB7_PCINT7_OC0A_OC1C_17") (pintype "bidirectional"))
    )
    (net (code "31") (name "/SDCLK") (class "Default")
      (node (ref "J10") (pin "5") (pinfunction "CLK_5") (pintype "input"))
      (node (ref "U4") (pin "3") (pinfunction "A2_3") (pintype "bidirectional"))
    )
    (net (code "32") (name "/SDCS") (class "Default")
      (node (ref "U4") (pin "10") (pinfunction "B4_10") (pintype "bidirectional"))
      (node (ref "U5") (pin "10") (pinfunction "PB0_SS_PCINT0_10") (pintype "bidirectional"))
    )
    (net (code "33") (name "/SDCSH") (class "Default")
      (node (ref "J10") (pin "2") (pinfunction "DAT3/CS_2") (pintype "bidirectional"))
      (node (ref "U4") (pin "5") (pinfunction "A4_5") (pintype "bidirectional"))
    )
    (net (code "34") (name "/SDDI") (class "Default")
      (node (ref "J10") (pin "3") (pinfunction "CMD/DI_3") (pintype "input"))
      (node (ref "U4") (pin "4") (pinfunction "A3_4") (pintype "bidirectional"))
    )
    (net (code "35") (name "/SDDO") (class "Default")
      (node (ref "J10") (pin "7") (pinfunction "DAT0/DO_7") (pintype "bidirectional"))
      (node (ref "U4") (pin "2") (pinfunction "A1_2") (pintype "bidirectional"))
    )
    (net (code "36") (name "/USB_DN") (class "Default")
      (node (ref "J11") (pin "D-") (pinfunction "D-_D-") (pintype "bidirectional"))
      (node (ref "R6") (pin "1") (pinfunction "1_1") (pintype "passive"))
      (node (ref "U2") (pin "3") (pinfunction "IO2_3") (pintype "bidirectional"))
    )
    (net (code "37") (name "/USB_DP") (class "Default")
      (node (ref "J11") (pin "D+") (pinfunction "D+_D+") (pintype "bidirectional"))
      (node (ref "R7") (pin "1") (pinfunction "1_1") (pintype "passive"))
      (node (ref "U2") (pin "2") (pinfunction "IO1_2") (pintype "bidirectional"))
    )
    (net (code "38") (name "/VBUS") (class "Default")
      (node (ref "C4") (pin "2") (pinfunction "2_2") (pintype "passive"))
      (node (ref "J11") (pin "VBUS") (pinfunction "VBUS_VBUS") (pintype "bidirectional"))
      (node (ref "SJ1") (pin "1") (pinfunction "1_1") (pintype "passive"))
      (node (ref "U2") (pin "4") (pinfunction "VCC_4") (pintype "power_in"))
      (node (ref "U5") (pin "3") (pinfunction "UVCC_3") (pintype "power_in"))
      (node (ref "U5") (pin "8") (pinfunction "VBUS_8") (pintype "bidirectional"))
    )
    (net (code "39") (name "/X-DIR") (class "Default")
      (node (ref "P1") (pin "DIR") (pinfunction "DIR_DIR") (pintype "bidirectional"))
      (node (ref "U5") (pin "49") (pinfunction "PA2_AD2_49") (pintype "bidirectional"))
    )
    (net (code "40") (name "/X-STEP") (class "Default")
      (node (ref "P1") (pin "STEP") (pinfunction "STEP_STEP") (pintype "bidirectional"))
      (node (ref "U5") (pin "50") (pinfunction "PA1_AD1_50") (pintype "bidirectional"))
    )
    (net (code "41") (name "/X-STOP") (class "Default")
      (node (ref "JP8") (pin "1") (pinfunction "1_1") (pintype "passive"))
      (node (ref "U5") (pin "16") (pinfunction "PB6_PCINT6_OC1B_16") (pintype "bidirectional"))
    )
    (net (code "42") (name "/XTAL1") (class "Default")
      (node (ref "C13") (pin "2") (pinfunction "2_2") (pintype "passive"))
      (node (ref "U5") (pin "24") (pinfunction "XTAL1_24") (pintype "passive"))
      (node (ref "X1") (pin "P$2") (pinfunction "2_P$2") (pintype "passive"))
    )
    (net (code "43") (name "/XTAL2") (class "Default")
      (node (ref "C12") (pin "2") (pinfunction "2_2") (pintype "passive"))
      (node (ref "U5") (pin "23") (pinfunction "XTAL2_23") (pintype "passive"))
      (node (ref "X1") (pin "P$1") (pinfunction "1_P$1") (pintype "passive"))
    )
    (net (code "44") (name "/Y-DIR") (class "Default")
      (node (ref "P2") (pin "DIR") (pinfunction "DIR_DIR") (pintype "bidirectional"))
      (node (ref "U5") (pin "46") (pinfunction "PA5_AD5_46") (pintype "bidirectional"))
    )
    (net (code "45") (name "/Y-STEP") (class "Default")
      (node (ref "P2") (pin "STEP") (pinfunction "STEP_STEP") (pintype "bidirectional"))
      (node (ref "U5") (pin "47") (pinfunction "PA4_AD4_47") (pintype "bidirectional"))
    )
    (net (code "46") (name "/Y-STOP") (class "Default")
      (node (ref "JP9") (pin "1") (pinfunction "1_1") (pintype "passive"))
      (node (ref "U5") (pin "15") (pinfunction "PB5_PCINT5_OC1A_15") (pintype "bidirectional"))
    )
    (net (code "47") (name "/Z-DIR") (class "Default")
      (node (ref "P3") (pin "DIR") (pinfunction "DIR_DIR") (pintype "bidirectional"))
      (node (ref "U5") (pin "42") (pinfunction "PC7_A15_IC3_CLK0_42") (pintype "bidirectional"))
    )
    (net (code "48") (name "/Z-STEP") (class "Default")
      (node (ref "P3") (pin "STEP") (pinfunction "STEP_STEP") (pintype "bidirectional"))
      (node (ref "U5") (pin "44") (pinfunction "PA7_AD7_44") (pintype "bidirectional"))
    )
    (net (code "49") (name "/Z-STOP") (class "Default")
      (node (ref "Q3") (pin "3") (pinfunction "C_3") (pintype "passive"))
      (node (ref "U5") (pin "1") (pinfunction "PE6_INT6_AIN0_1") (pintype "bidirectional"))
    )
    (net (code "50") (name "/~{E1-ENABLE}") (class "Default")
      (node (ref "P4") (pin "!EN") (pinfunction "~{ENABLE}_!EN") (pintype "input"))
      (node (ref "R19") (pin "2") (pinfunction "2_2") (pintype "passive"))
      (node (ref "U5") (pin "38") (pinfunction "PC3_A11_T3_38") (pintype "bidirectional"))
    )
    (net (code "51") (name "/~{E2-ENABLE}") (class "Default")
      (node (ref "U5") (pin "35") (pinfunction "PC0_A8_35") (pintype "bidirectional"))
    )
    (net (code "52") (name "/~{HOTBED}") (class "Default")
      (node (ref "R12") (pin "1") (pinfunction "1_1") (pintype "passive"))
      (node (ref "R13") (pin "1") (pinfunction "1_1") (pintype "passive"))
      (node (ref "U5") (pin "39") (pinfunction "PC4_A12_OC3C_39") (pintype "bidirectional"))
    )
    (net (code "53") (name "/~{HOTEND-1}") (class "Default")
      (node (ref "R8") (pin "1") (pinfunction "1_1") (pintype "passive"))
      (node (ref "R9") (pin "1") (pinfunction "1_1") (pintype "passive"))
      (node (ref "U5") (pin "40") (pinfunction "PC5_A13_OC3B_40") (pintype "bidirectional"))
    )
    (net (code "54") (name "/~{HOTEND-2}") (class "Default")
      (node (ref "U5") (pin "58") (pinfunction "PF3_ADC3_58") (pintype "bidirectional"))
    )
    (net (code "55") (name "/~{PWM-FAN}") (class "Default")
      (node (ref "R2") (pin "1") (pinfunction "1_1") (pintype "passive"))
      (node (ref "R3") (pin "1") (pinfunction "1_1") (pintype "passive"))
      (node (ref "U5") (pin "41") (pinfunction "PC6_A14_OC3A_41") (pintype "bidirectional"))
    )
    (net (code "56") (name "/~{RESET}") (class "Default")
      (node (ref "JP1") (pin "2") (pinfunction "2_2") (pintype "passive"))
      (node (ref "R10") (pin "1") (pinfunction "1_1") (pintype "passive"))
      (node (ref "S1") (pin "3") (pinfunction "3_3") (pintype "passive"))
      (node (ref "S1") (pin "4") (pinfunction "4_4") (pintype "passive"))
      (node (ref "U5") (pin "20") (pinfunction "/RESET_20") (pintype "bidirectional"))
    )
    (net (code "57") (name "/~{X-ENABLE}") (class "Default")
      (node (ref "P1") (pin "!EN") (pinfunction "~{ENABLE}_!EN") (pintype "input"))
      (node (ref "R17") (pin "2") (pinfunction "2_2") (pintype "passive"))
      (node (ref "U5") (pin "51") (pinfunction "PA0_AD0_51") (pintype "bidirectional"))
    )
    (net (code "58") (name "/~{Y-ENABLE}") (class "Default")
      (node (ref "P2") (pin "!EN") (pinfunction "~{ENABLE}_!EN") (pintype "input"))
      (node (ref "R16") (pin "2") (pinfunction "2_2") (pintype "passive"))
      (node (ref "U5") (pin "48") (pinfunction "PA3_AD3_48") (pintype "bidirectional"))
    )
    (net (code "59") (name "/~{Z-ENABLE}") (class "Default")
      (node (ref "P3") (pin "!EN") (pinfunction "~{ENABLE}_!EN") (pintype "input"))
      (node (ref "R18") (pin "2") (pinfunction "2_2") (pintype "passive"))
      (node (ref "U5") (pin "45") (pinfunction "PA6_AD6_45") (pintype "bidirectional"))
    )
    (net (code "60") (name "5V") (class "Default")
      (node (ref "C2") (pin "1") (pinfunction "1_1") (pintype "passive"))
      (node (ref "C5") (pin "2") (pinfunction "2_2") (pintype "passive"))
      (node (ref "C6") (pin "2") (pinfunction "2_2") (pintype "passive"))
      (node (ref "C7") (pin "1") (pinfunction "1_1") (pintype "passive"))
      (node (ref "C9") (pin "1") (pinfunction "1_1") (pintype "passive"))
      (node (ref "J16") (pin "2") (pinfunction "2_2") (pintype "passive"))
      (node (ref "JP1") (pin "5") (pinfunction "5_5") (pintype "passive"))
      (node (ref "JP6") (pin "3") (pinfunction "3_3") (pintype "passive"))
      (node (ref "JP7") (pin "2") (pinfunction "2_2") (pintype "passive"))
      (node (ref "L1") (pin "2") (pinfunction "2_2") (pintype "passive"))
      (node (ref "P1") (pin "VDD") (pinfunction "VDD_VDD") (pintype "power_in"))
      (node (ref "P2") (pin "VDD") (pinfunction "VDD_VDD") (pintype "power_in"))
      (node (ref "P3") (pin "VDD") (pinfunction "VDD_VDD") (pintype "power_in"))
      (node (ref "P4") (pin "VDD") (pinfunction "VDD_VDD") (pintype "power_in"))
      (node (ref "R1") (pin "2") (pinfunction "2_2") (pintype "passive"))
      (node (ref "R10") (pin "2") (pinfunction "2_2") (pintype "passive"))
      (node (ref "R11") (pin "2") (pinfunction "2_2") (pintype "passive"))
      (node (ref "R14") (pin "2") (pinfunction "2_2") (pintype "passive"))
      (node (ref "R15") (pin "2") (pinfunction "2_2") (pintype "passive"))
      (node (ref "R16") (pin "1") (pinfunction "1_1") (pintype "passive"))
      (node (ref "R17") (pin "1") (pinfunction "1_1") (pintype "passive"))
      (node (ref "R18") (pin "1") (pinfunction "1_1") (pintype "passive"))
      (node (ref "R19") (pin "1") (pinfunction "1_1") (pintype "passive"))
      (node (ref "R4") (pin "1") (pinfunction "1_1") (pintype "passive"))
      (node (ref "SJ1") (pin "2") (pinfunction "2_2") (pintype "passive"))
      (node (ref "SJ10") (pin "2") (pinfunction "2_2") (pintype "passive"))
      (node (ref "SJ11") (pin "2") (pinfunction "2_2") (pintype "passive"))
      (node (ref "SJ12") (pin "2") (pinfunction "2_2") (pintype "passive"))
      (node (ref "SJ13") (pin "2") (pinfunction "2_2") (pintype "passive"))
      (node (ref "SJ2") (pin "2") (pinfunction "2_2") (pintype "passive"))
      (node (ref "SJ3") (pin "2") (pinfunction "2_2") (pintype "passive"))
      (node (ref "SJ4") (pin "2") (pinfunction "2_2") (pintype "passive"))
      (node (ref "SJ5") (pin "2") (pinfunction "2_2") (pintype "passive"))
      (node (ref "SJ6") (pin "2") (pinfunction "2_2") (pintype "passive"))
      (node (ref "SJ7") (pin "2") (pinfunction "2_2") (pintype "passive"))
      (node (ref "SJ8") (pin "2") (pinfunction "2_2") (pintype "passive"))
      (node (ref "SJ9") (pin "2") (pinfunction "2_2") (pintype "passive"))
      (node (ref "U3") (pin "1") (pinfunction "IN_1") (pintype "power_in"))
      (node (ref "U4") (pin "14") (pinfunction "VCCB_14") (pintype "power_in"))
      (node (ref "U5") (pin "21") (pinfunction "VCC_21") (pintype "power_in"))
      (node (ref "U5") (pin "52") (pinfunction "VCC_52") (pintype "power_in"))
      (node (ref "U5") (pin "62") (pinfunction "AREF_62") (pintype "power_in"))
      (node (ref "U5") (pin "64") (pinfunction "AVCC_64") (pintype "power_in"))
    )
    (net (code "61") (name "12V") (class "Default")
      (node (ref "C1") (pin "1") (pinfunction "1_1") (pintype "passive"))
      (node (ref "C11") (pin "+") (pinfunction "+_+") (pintype "passive"))
      (node (ref "C14") (pin "+") (pinfunction "+_+") (pintype "passive"))
      (node (ref "C17") (pin "+") (pinfunction "+_+") (pintype "passive"))
      (node (ref "C18") (pin "+") (pinfunction "+_+") (pintype "passive"))
      (node (ref "C19") (pin "+") (pinfunction "+_+") (pintype "passive"))
      (node (ref "C20") (pin "+") (pinfunction "+_+") (pintype "passive"))
      (node (ref "F2") (pin "P$3") (pinfunction "P$3_P$3") (pintype "passive"))
      (node (ref "F2") (pin "P$4") (pinfunction "P$4_P$4") (pintype "passive"))
      (node (ref "J12") (pin "1") (pinfunction "1_1") (pintype "passive"))
      (node (ref "J14") (pin "3") (pinfunction "3_3") (pintype "power_in"))
      (node (ref "J14") (pin "4") (pinfunction "4_4") (pintype "power_in"))
      (node (ref "J16") (pin "3") (pinfunction "3_3") (pintype "passive"))
      (node (ref "J17") (pin "3") (pinfunction "3_3") (pintype "power_in"))
      (node (ref "J17") (pin "4") (pinfunction "4_4") (pintype "power_in"))
      (node (ref "J8") (pin "1") (pinfunction "1_1") (pintype "passive"))
      (node (ref "J9") (pin "1") (pinfunction "1_1") (pintype "passive"))
      (node (ref "JP6") (pin "1") (pinfunction "1_1") (pintype "passive"))
      (node (ref "JP7") (pin "4") (pinfunction "4_4") (pintype "passive"))
      (node (ref "P1") (pin "VMOT") (pinfunction "VMOT_VMOT") (pintype "power_in"))
      (node (ref "P2") (pin "VMOT") (pinfunction "VMOT_VMOT") (pintype "power_in"))
      (node (ref "P3") (pin "VMOT") (pinfunction "VMOT_VMOT") (pintype "power_in"))
      (node (ref "P4") (pin "VMOT") (pinfunction "VMOT_VMOT") (pintype "power_in"))
      (node (ref "U1") (pin "4") (pinfunction "~{SHDN}_4") (pintype "input"))
      (node (ref "U1") (pin "5") (pinfunction "VIN_5") (pintype "power_in"))
    )
    (net (code "62") (name "GND") (class "Default")
      (node (ref "C1") (pin "2") (pinfunction "2_2") (pintype "passive"))
      (node (ref "C10") (pin "2") (pinfunction "2_2") (pintype "passive"))
      (node (ref "C11") (pin "-") (pinfunction "-_-") (pintype "passive"))
      (node (ref "C12") (pin "1") (pinfunction "1_1") (pintype "passive"))
      (node (ref "C13") (pin "1") (pinfunction "1_1") (pintype "passive"))
      (node (ref "C14") (pin "-") (pinfunction "-_-") (pintype "passive"))
      (node (ref "C15") (pin "1") (pinfunction "1_1") (pintype "passive"))
      (node (ref "C16") (pin "1") (pinfunction "1_1") (pintype "passive"))
      (node (ref "C17") (pin "-") (pinfunction "-_-") (pintype "passive"))
      (node (ref "C18") (pin "-") (pinfunction "-_-") (pintype "passive"))
      (node (ref "C19") (pin "-") (pinfunction "-_-") (pintype "passive"))
      (node (ref "C2") (pin "2") (pinfunction "2_2") (pintype "passive"))
      (node (ref "C20") (pin "-") (pinfunction "-_-") (pintype "passive"))
      (node (ref "C4") (pin "1") (pinfunction "1_1") (pintype "passive"))
      (node (ref "C5") (pin "1") (pinfunction "1_1") (pintype "passive"))
      (node (ref "C6") (pin "1") (pinfunction "1_1") (pintype "passive"))
      (node (ref "C7") (pin "2") (pinfunction "2_2") (pintype "passive"))
      (node (ref "C8") (pin "1") (pinfunction "1_1") (pintype "passive"))
      (node (ref "C9") (pin "2") (pinfunction "2_2") (pintype "passive"))
      (node (ref "D1") (pin "A") (pinfunction "A_A") (pintype "passive"))
      (node (ref "D2") (pin "A") (pinfunction "A_A") (pintype "passive"))
      (node (ref "J1") (pin "1") (pinfunction "+_1") (pintype "passive"))
      (node (ref "J1") (pin "2") (pinfunction "-_2") (pintype "passive"))
      (node (ref "J10") (pin "6") (pinfunction "GND_6") (pintype "power_in"))
      (node (ref "J10") (pin "C1") (pinfunction "SHEILD_C1") (pintype "bidirectional"))
      (node (ref "J10") (pin "C2") (pinfunction "SHIELD_C2") (pintype "bidirectional"))
      (node (ref "J10") (pin "C3") (pinfunction "SHIELD_C3") (pintype "bidirectional"))
      (node (ref "J10") (pin "C4") (pinfunction "SHIELD_C4") (pintype "bidirectional"))
      (node (ref "J10") (pin "CD1") (pinfunction "CD1_CD1") (pintype "bidirectional"))
      (node (ref "J11") (pin "GND") (pinfunction "GND_GND") (pintype "bidirectional"))
      (node (ref "J11") (pin "GND1") (pinfunction "GND_GND1") (pintype "bidirectional"))
      (node (ref "J11") (pin "GND2") (pinfunction "GND_GND2") (pintype "bidirectional"))
      (node (ref "J11") (pin "GND3") (pinfunction "GND_GND3") (pintype "bidirectional"))
      (node (ref "J11") (pin "GND4") (pinfunction "GND_GND4") (pintype "bidirectional"))
      (node (ref "J11") (pin "GND5") (pinfunction "GND_GND5") (pintype "bidirectional"))
      (node (ref "J11") (pin "GND6") (pinfunction "GND_GND6") (pintype "bidirectional"))
      (node (ref "J11") (pin "GND7") (pinfunction "GND_GND7") (pintype "bidirectional"))
      (node (ref "J11") (pin "GND8") (pinfunction "GND_GND8") (pintype "bidirectional"))
      (node (ref "J13") (pin "3") (pinfunction "3_3") (pintype "power_in"))
      (node (ref "J13") (pin "4") (pinfunction "4_4") (pintype "power_in"))
      (node (ref "J15") (pin "4") (pinfunction "S_4") (pintype "passive"))
      (node (ref "J15") (pin "5") (pinfunction "S_5") (pintype "passive"))
      (node (ref "J15") (pin "6") (pinfunction "S_6") (pintype "passive"))
      (node (ref "J16") (pin "1") (pinfunction "1_1") (pintype "passive"))
      (node (ref "J18") (pin "2") (pinfunction "2_2") (pintype "passive"))
      (node (ref "J19") (pin "2") (pinfunction "2_2") (pintype "passive"))
      (node (ref "J2") (pin "1") (pinfunction "+_1") (pintype "passive"))
      (node (ref "J2") (pin "2") (pinfunction "-_2") (pintype "passive"))
      (node (ref "J3") (pin "1") (pinfunction "+_1") (pintype "passive"))
      (node (ref "J3") (pin "2") (pinfunction "-_2") (pintype "passive"))
      (node (ref "J4") (pin "1") (pinfunction "+_1") (pintype "passive"))
      (node (ref "J4") (pin "2") (pinfunction "-_2") (pintype "passive"))
      (node (ref "J5") (pin "1") (pinfunction "+_1") (pintype "passive"))
      (node (ref "J5") (pin "2") (pinfunction "-_2") (pintype "passive"))
      (node (ref "J6") (pin "1") (pinfunction "+_1") (pintype "passive"))
      (node (ref "J6") (pin "2") (pinfunction "-_2") (pintype "passive"))
      (node (ref "J7") (pin "1") (pinfunction "+_1") (pintype "passive"))
      (node (ref "J7") (pin "2") (pinfunction "-_2") (pintype "passive"))
      (node (ref "J8") (pin "2") (pinfunction "2_2") (pintype "passive"))
      (node (ref "J9") (pin "2") (pinfunction "2_2") (pintype "passive"))
      (node (ref "JP1") (pin "1") (pinfunction "1_1") (pintype "passive"))
      (node (ref "JP10") (pin "3") (pinfunction "3_3") (pintype "passive"))
      (node (ref "JP5") (pin "2") (pinfunction "2_2") (pintype "passive"))
      (node (ref "JP7") (pin "3") (pinfunction "3_3") (pintype "passive"))
      (node (ref "JP8") (pin "3") (pinfunction "3_3") (pintype "passive"))
      (node (ref "JP9") (pin "3") (pinfunction "3_3") (pintype "passive"))
      (node (ref "LED1") (pin "C") (pinfunction "C_C") (pintype "passive"))
      (node (ref "P1") (pin "GNDMOT") (pinfunction "GNDMOT_GNDMOT") (pintype "power_in"))
      (node (ref "P1") (pin "GNDVDD") (pinfunction "GNDVDD_GNDVDD") (pintype "power_in"))
      (node (ref "P2") (pin "GNDMOT") (pinfunction "GNDMOT_GNDMOT") (pintype "power_in"))
      (node (ref "P2") (pin "GNDVDD") (pinfunction "GNDVDD_GNDVDD") (pintype "power_in"))
      (node (ref "P3") (pin "GNDMOT") (pinfunction "GNDMOT_GNDMOT") (pintype "power_in"))
      (node (ref "P3") (pin "GNDVDD") (pinfunction "GNDVDD_GNDVDD") (pintype "power_in"))
      (node (ref "P4") (pin "GNDMOT") (pinfunction "GNDMOT_GNDMOT") (pintype "power_in"))
      (node (ref "P4") (pin "GNDVDD") (pinfunction "GNDVDD_GNDVDD") (pintype "power_in"))
      (node (ref "Q1") (pin "2") (pinfunction "S_2") (pintype "passive"))
      (node (ref "Q2") (pin "1") (pinfunction "S1_1") (pintype "passive"))
      (node (ref "Q2") (pin "2") (pinfunction "S2_2") (pintype "passive"))
      (node (ref "Q2") (pin "3") (pinfunction "S3_3") (pintype "passive"))
      (node (ref "Q3") (pin "2") (pinfunction "E_2") (pintype "passive"))
      (node (ref "Q4") (pin "1") (pinfunction "S1_1") (pintype "passive"))
      (node (ref "Q4") (pin "2") (pinfunction "S2_2") (pintype "passive"))
      (node (ref "Q4") (pin "3") (pinfunction "S3_3") (pintype "passive"))
      (node (ref "R12") (pin "2") (pinfunction "2_2") (pintype "passive"))
      (node (ref "R2") (pin "2") (pinfunction "2_2") (pintype "passive"))
      (node (ref "R5") (pin "2") (pinfunction "2_2") (pintype "passive"))
      (node (ref "R8") (pin "2") (pinfunction "2_2") (pintype "passive"))
      (node (ref "S1") (pin "1") (pinfunction "1_1") (pintype "passive"))
      (node (ref "S1") (pin "2") (pinfunction "2_2") (pintype "passive"))
      (node (ref "SCREW1") (pin "GND") (pinfunction "P$1_GND") (pintype "bidirectional"))
      (node (ref "SCREW2") (pin "GND") (pinfunction "P$1_GND") (pintype "bidirectional"))
      (node (ref "SCREW3") (pin "GND") (pinfunction "P$1_GND") (pintype "bidirectional"))
      (node (ref "SCREW4") (pin "GND") (pinfunction "P$1_GND") (pintype "bidirectional"))
      (node (ref "U1") (pin "2") (pinfunction "GND_2") (pintype "power_in"))
      (node (ref "U2") (pin "1") (pinfunction "GND_1") (pintype "power_in"))
      (node (ref "U3") (pin "3") (pinfunction "GND_3") (pintype "power_in"))
      (node (ref "U4") (pin "7") (pinfunction "GND_7") (pintype "power_in"))
      (node (ref "U5") (pin "22") (pinfunction "GND_22") (pintype "power_in"))
      (node (ref "U5") (pin "53") (pinfunction "GND_53") (pintype "power_in"))
      (node (ref "U5") (pin "6") (pinfunction "UGND_6") (pintype "power_in"))
      (node (ref "U5") (pin "63") (pinfunction "AGND_63") (pintype "power_in"))
    )
    (net (code "63") (name "Net-(F1-PadP$2)") (class "Default")
      (node (ref "F1") (pin "P$2") (pinfunction "P$2_P$2") (pintype "passive"))
      (node (ref "J12") (pin "2") (pinfunction "2_2") (pintype "passive"))
    )
    (net (code "64") (name "Net-(J15A-S)") (class "Default")
      (node (ref "F2") (pin "P$1") (pinfunction "P$1_P$1") (pintype "passive"))
      (node (ref "F2") (pin "P$2") (pinfunction "P$2_P$2") (pintype "passive"))
      (node (ref "J13") (pin "1") (pinfunction "1_1") (pintype "power_in"))
      (node (ref "J13") (pin "2") (pinfunction "2_2") (pintype "power_in"))
      (node (ref "J15") (pin "1") (pinfunction "S_1") (pintype "passive"))
      (node (ref "J15") (pin "2") (pinfunction "S_2") (pintype "passive"))
      (node (ref "J15") (pin "3") (pinfunction "S_3") (pintype "passive"))
    )
    (net (code "65") (name "Net-(JP10-Pad2)") (class "Default")
      (node (ref "JP10") (pin "2") (pinfunction "2_2") (pintype "passive"))
      (node (ref "JP6") (pin "2") (pinfunction "2_2") (pintype "passive"))
      (node (ref "JP8") (pin "2") (pinfunction "2_2") (pintype "passive"))
      (node (ref "JP9") (pin "2") (pinfunction "2_2") (pintype "passive"))
    )
    (net (code "66") (name "Net-(LED1-PadA)") (class "Default")
      (node (ref "LED1") (pin "A") (pinfunction "A_A") (pintype "passive"))
      (node (ref "R1") (pin "1") (pinfunction "1_1") (pintype "passive"))
    )
    (net (code "67") (name "Net-(P1-MOT-1A)") (class "Default")
      (node (ref "JP11") (pin "3") (pinfunction "3_3") (pintype "passive"))
      (node (ref "P1") (pin "1A") (pinfunction "MOT-1A_1A") (pintype "power_in"))
    )
    (net (code "68") (name "Net-(P1-MOT-1B)") (class "Default")
      (node (ref "JP11") (pin "4") (pinfunction "4_4") (pintype "passive"))
      (node (ref "P1") (pin "1B") (pinfunction "MOT-1B_1B") (pintype "power_in"))
    )
    (net (code "69") (name "Net-(P1-MOT-2A)") (class "Default")
      (node (ref "JP11") (pin "2") (pinfunction "2_2") (pintype "passive"))
      (node (ref "P1") (pin "2A") (pinfunction "MOT-2A_2A") (pintype "power_in"))
    )
    (net (code "70") (name "Net-(P1-MOT-2B)") (class "Default")
      (node (ref "JP11") (pin "1") (pinfunction "1_1") (pintype "passive"))
      (node (ref "P1") (pin "2B") (pinfunction "MOT-2B_2B") (pintype "power_in"))
    )
    (net (code "71") (name "Net-(P1-PadMS1)") (class "Default")
      (node (ref "P1") (pin "MS1") (pinfunction "MS1_MS1") (pintype "input"))
      (node (ref "SJ10") (pin "1") (pinfunction "1_1") (pintype "passive"))
    )
    (net (code "72") (name "Net-(P1-PadMS2)") (class "Default")
      (node (ref "P1") (pin "MS2") (pinfunction "MS2_MS2") (pintype "input"))
      (node (ref "SJ6") (pin "1") (pinfunction "1_1") (pintype "passive"))
    )
    (net (code "73") (name "Net-(P1-PadMS3)") (class "Default")
      (node (ref "P1") (pin "MS3") (pinfunction "MS3_MS3") (pintype "input"))
      (node (ref "SJ2") (pin "1") (pinfunction "1_1") (pintype "passive"))
    )
    (net (code "74") (name "Net-(P1-~{RESET})") (class "Default")
      (node (ref "P1") (pin "!RST") (pinfunction "~{RESET}_!RST") (pintype "input"))
      (node (ref "P1") (pin "!SLP") (pinfunction "~{SLEEP}_!SLP") (pintype "input"))
    )
    (net (code "75") (name "Net-(P2-MOT-1A)") (class "Default")
      (node (ref "JP12") (pin "3") (pinfunction "3_3") (pintype "passive"))
      (node (ref "P2") (pin "1A") (pinfunction "MOT-1A_1A") (pintype "power_in"))
    )
    (net (code "76") (name "Net-(P2-MOT-1B)") (class "Default")
      (node (ref "JP12") (pin "4") (pinfunction "4_4") (pintype "passive"))
      (node (ref "P2") (pin "1B") (pinfunction "MOT-1B_1B") (pintype "power_in"))
    )
    (net (code "77") (name "Net-(P2-MOT-2A)") (class "Default")
      (node (ref "JP12") (pin "2") (pinfunction "2_2") (pintype "passive"))
      (node (ref "P2") (pin "2A") (pinfunction "MOT-2A_2A") (pintype "power_in"))
    )
    (net (code "78") (name "Net-(P2-MOT-2B)") (class "Default")
      (node (ref "JP12") (pin "1") (pinfunction "1_1") (pintype "passive"))
      (node (ref "P2") (pin "2B") (pinfunction "MOT-2B_2B") (pintype "power_in"))
    )
    (net (code "79") (name "Net-(P2-PadMS1)") (class "Default")
      (node (ref "P2") (pin "MS1") (pinfunction "MS1_MS1") (pintype "input"))
      (node (ref "SJ11") (pin "1") (pinfunction "1_1") (pintype "passive"))
    )
    (net (code "80") (name "Net-(P2-PadMS2)") (class "Default")
      (node (ref "P2") (pin "MS2") (pinfunction "MS2_MS2") (pintype "input"))
      (node (ref "SJ7") (pin "1") (pinfunction "1_1") (pintype "passive"))
    )
    (net (code "81") (name "Net-(P2-PadMS3)") (class "Default")
      (node (ref "P2") (pin "MS3") (pinfunction "MS3_MS3") (pintype "input"))
      (node (ref "SJ3") (pin "1") (pinfunction "1_1") (pintype "passive"))
    )
    (net (code "82") (name "Net-(P2-~{RESET})") (class "Default")
      (node (ref "P2") (pin "!RST") (pinfunction "~{RESET}_!RST") (pintype "input"))
      (node (ref "P2") (pin "!SLP") (pinfunction "~{SLEEP}_!SLP") (pintype "input"))
    )
    (net (code "83") (name "Net-(P3-MOT-1A)") (class "Default")
      (node (ref "JP14") (pin "3") (pinfunction "3_3") (pintype "passive"))
      (node (ref "P3") (pin "1A") (pinfunction "MOT-1A_1A") (pintype "power_in"))
    )
    (net (code "84") (name "Net-(P3-MOT-1B)") (class "Default")
      (node (ref "JP14") (pin "4") (pinfunction "4_4") (pintype "passive"))
      (node (ref "P3") (pin "1B") (pinfunction "MOT-1B_1B") (pintype "power_in"))
    )
    (net (code "85") (name "Net-(P3-MOT-2A)") (class "Default")
      (node (ref "JP14") (pin "2") (pinfunction "2_2") (pintype "passive"))
      (node (ref "P3") (pin "2A") (pinfunction "MOT-2A_2A") (pintype "power_in"))
    )
    (net (code "86") (name "Net-(P3-MOT-2B)") (class "Default")
      (node (ref "JP14") (pin "1") (pinfunction "1_1") (pintype "passive"))
      (node (ref "P3") (pin "2B") (pinfunction "MOT-2B_2B") (pintype "power_in"))
    )
    (net (code "87") (name "Net-(P3-PadMS1)") (class "Default")
      (node (ref "P3") (pin "MS1") (pinfunction "MS1_MS1") (pintype "input"))
      (node (ref "SJ12") (pin "1") (pinfunction "1_1") (pintype "passive"))
    )
    (net (code "88") (name "Net-(P3-PadMS2)") (class "Default")
      (node (ref "P3") (pin "MS2") (pinfunction "MS2_MS2") (pintype "input"))
      (node (ref "SJ8") (pin "1") (pinfunction "1_1") (pintype "passive"))
    )
    (net (code "89") (name "Net-(P3-PadMS3)") (class "Default")
      (node (ref "P3") (pin "MS3") (pinfunction "MS3_MS3") (pintype "input"))
      (node (ref "SJ4") (pin "1") (pinfunction "1_1") (pintype "passive"))
    )
    (net (code "90") (name "Net-(P3-~{RESET})") (class "Default")
      (node (ref "P3") (pin "!RST") (pinfunction "~{RESET}_!RST") (pintype "input"))
      (node (ref "P3") (pin "!SLP") (pinfunction "~{SLEEP}_!SLP") (pintype "input"))
    )
    (net (code "91") (name "Net-(P4-MOT-1A)") (class "Default")
      (node (ref "JP13") (pin "3") (pinfunction "3_3") (pintype "passive"))
      (node (ref "P4") (pin "1A") (pinfunction "MOT-1A_1A") (pintype "power_in"))
    )
    (net (code "92") (name "Net-(P4-MOT-1B)") (class "Default")
      (node (ref "JP13") (pin "4") (pinfunction "4_4") (pintype "passive"))
      (node (ref "P4") (pin "1B") (pinfunction "MOT-1B_1B") (pintype "power_in"))
    )
    (net (code "93") (name "Net-(P4-MOT-2A)") (class "Default")
      (node (ref "JP13") (pin "2") (pinfunction "2_2") (pintype "passive"))
      (node (ref "P4") (pin "2A") (pinfunction "MOT-2A_2A") (pintype "power_in"))
    )
    (net (code "94") (name "Net-(P4-MOT-2B)") (class "Default")
      (node (ref "JP13") (pin "1") (pinfunction "1_1") (pintype "passive"))
      (node (ref "P4") (pin "2B") (pinfunction "MOT-2B_2B") (pintype "power_in"))
    )
    (net (code "95") (name "Net-(P4-PadMS1)") (class "Default")
      (node (ref "P4") (pin "MS1") (pinfunction "MS1_MS1") (pintype "input"))
      (node (ref "SJ13") (pin "1") (pinfunction "1_1") (pintype "passive"))
    )
    (net (code "96") (name "Net-(P4-PadMS2)") (class "Default")
      (node (ref "P4") (pin "MS2") (pinfunction "MS2_MS2") (pintype "input"))
      (node (ref "SJ9") (pin "1") (pinfunction "1_1") (pintype "passive"))
    )
    (net (code "97") (name "Net-(P4-PadMS3)") (class "Default")
      (node (ref "P4") (pin "MS3") (pinfunction "MS3_MS3") (pintype "input"))
      (node (ref "SJ5") (pin "1") (pinfunction "1_1") (pintype "passive"))
    )
    (net (code "98") (name "Net-(P4-~{RESET})") (class "Default")
      (node (ref "P4") (pin "!RST") (pinfunction "~{RESET}_!RST") (pintype "input"))
      (node (ref "P4") (pin "!SLP") (pinfunction "~{SLEEP}_!SLP") (pintype "input"))
    )
    (net (code "99") (name "Net-(Q1-D)") (class "Default")
      (node (ref "D1") (pin "C") (pinfunction "C_C") (pintype "passive"))
      (node (ref "F1") (pin "P$1") (pinfunction "P$1_P$1") (pintype "passive"))
      (node (ref "Q1") (pin "3") (pinfunction "D_3") (pintype "passive"))
    )
    (net (code "100") (name "Net-(Q1-G)") (class "Default")
      (node (ref "Q1") (pin "1") (pinfunction "G_1") (pintype "passive"))
      (node (ref "R3") (pin "2") (pinfunction "2_2") (pintype "passive"))
    )
    (net (code "101") (name "Net-(Q2-D)") (class "Default")
      (node (ref "J14") (pin "1") (pinfunction "1_1") (pintype "power_in"))
      (node (ref "J14") (pin "2") (pinfunction "2_2") (pintype "power_in"))
      (node (ref "Q2") (pin "5-8") (pinfunction "D_5-8") (pintype "passive"))
    )
    (net (code "102") (name "Net-(Q2-G)") (class "Default")
      (node (ref "Q2") (pin "4") (pinfunction "G_4") (pintype "passive"))
      (node (ref "R9") (pin "2") (pinfunction "2_2") (pintype "passive"))
    )
    (net (code "103") (name "Net-(Q3-B)") (class "Default")
      (node (ref "JP7") (pin "1") (pinfunction "1_1") (pintype "passive"))
      (node (ref "Q3") (pin "1") (pinfunction "B_1") (pintype "passive"))
    )
    (net (code "104") (name "Net-(Q4-D)") (class "Default")
      (node (ref "J17") (pin "1") (pinfunction "1_1") (pintype "power_in"))
      (node (ref "J17") (pin "2") (pinfunction "2_2") (pintype "power_in"))
      (node (ref "Q4") (pin "5-8") (pinfunction "D_5-8") (pintype "passive"))
    )
    (net (code "105") (name "Net-(Q4-G)") (class "Default")
      (node (ref "Q4") (pin "4") (pinfunction "G_4") (pintype "passive"))
      (node (ref "R13") (pin "2") (pinfunction "2_2") (pintype "passive"))
    )
    (net (code "106") (name "Net-(U1-CB)") (class "Default")
      (node (ref "C3") (pin "2") (pinfunction "2_2") (pintype "passive"))
      (node (ref "U1") (pin "1") (pinfunction "CB_1") (pintype "passive"))
    )
    (net (code "107") (name "Net-(U1-FB)") (class "Default")
      (node (ref "R4") (pin "2") (pinfunction "2_2") (pintype "passive"))
      (node (ref "R5") (pin "1") (pinfunction "1_1") (pintype "passive"))
      (node (ref "U1") (pin "3") (pinfunction "FB_3") (pintype "passive"))
    )
    (net (code "108") (name "Net-(U1-SW)") (class "Default")
      (node (ref "C3") (pin "1") (pinfunction "1_1") (pintype "passive"))
      (node (ref "D2") (pin "C") (pinfunction "C_C") (pintype "passive"))
      (node (ref "L1") (pin "1") (pinfunction "1_1") (pintype "passive"))
      (node (ref "U1") (pin "6") (pinfunction "SW_6") (pintype "passive"))
    )
    (net (code "109") (name "Net-(U5-D+)") (class "Default")
      (node (ref "R7") (pin "2") (pinfunction "2_2") (pintype "passive"))
      (node (ref "U5") (pin "5") (pinfunction "D+_5") (pintype "bidirectional"))
    )
    (net (code "110") (name "Net-(U5-D-)") (class "Default")
      (node (ref "R6") (pin "2") (pinfunction "2_2") (pintype "passive"))
      (node (ref "U5") (pin "4") (pinfunction "D-_4") (pintype "bidirectional"))
    )
    (net (code "111") (name "Net-(U5-UCAP)") (class "Default")
      (node (ref "C8") (pin "2") (pinfunction "2_2") (pintype "passive"))
      (node (ref "U5") (pin "7") (pinfunction "UCAP_7") (pintype "power_in"))
    )
    (net (code "112") (name "unconnected-(J10-DAT1-Pad8)") (class "Default")
      (node (ref "J10") (pin "8") (pinfunction "DAT1_8") (pintype "bidirectional"))
    )
    (net (code "113") (name "unconnected-(J10-DAT2-Pad1)") (class "Default")
      (node (ref "J10") (pin "1") (pinfunction "DAT2_1") (pintype "bidirectional"))
    )
  )
)
